# JacdacPinHeaders_45.net
KiCad netlist of a schematic drawn in Altium Designer
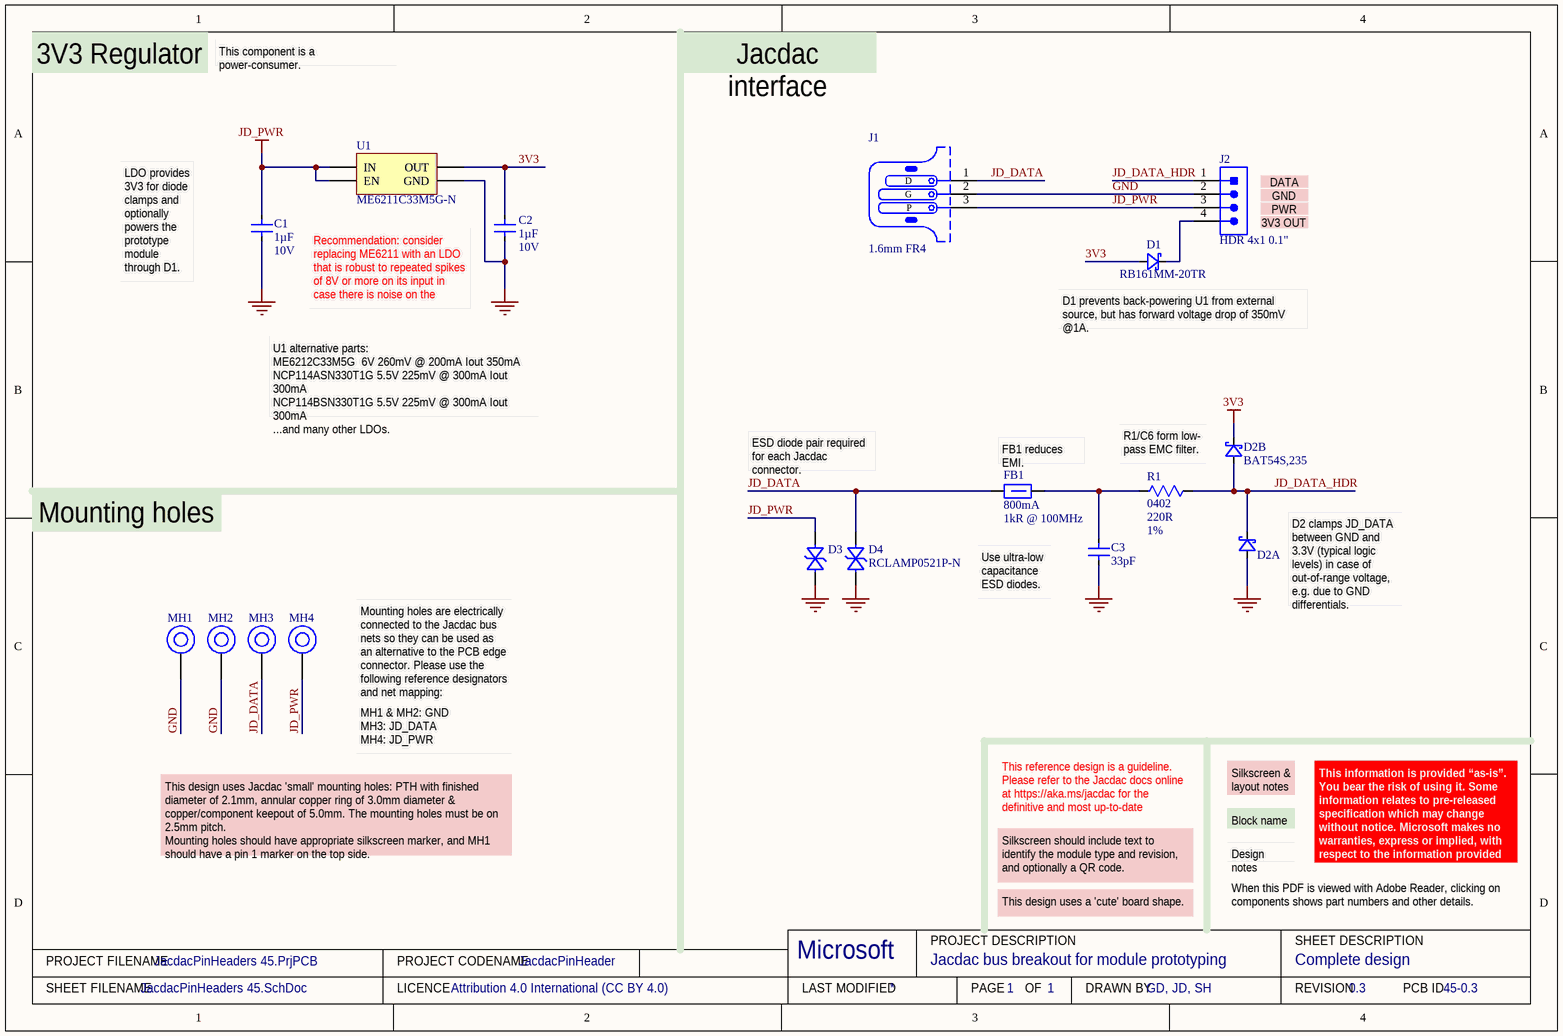
[diagram p0: JacdacPinHeaders 45.SchDoc]

(export (version "E")
  (design (tool "Eeschema 10.0.6"))
  (components
    (comp (ref "C1")
      (value "CL05A105KP5NNNC")
      (footprint "C0402_0.55MM - without outline")
      (description "CAP CER 1UF 10V X5R 0402")
      (fields
        (field (name "MANUFACTURER") "Samsung")
        (field (name "TOLERANCE") "10%")
        (field (name "CAPACITANCE") "1µF")
        (field (name "VOLTAGE RATING") "10V")
        (field (name "CREATED") "DG")
        (field (name "CHECKED") "?")
      )
      (libsource (lib "Samsung") (part "CL05A105KP5NNNC"))
    )
    (comp (ref "C2")
      (value "CL05A105KP5NNNC")
      (footprint "C0402_0.55MM - without outline")
      (description "CAP CER 1UF 10V X5R 0402")
      (fields
        (field (name "MANUFACTURER") "Samsung")
        (field (name "TOLERANCE") "10%")
        (field (name "CAPACITANCE") "1µF")
        (field (name "VOLTAGE RATING") "10V")
        (field (name "CREATED") "DG")
        (field (name "CHECKED") "?")
      )
      (libsource (lib "Samsung") (part "CL05A105KP5NNNC"))
    )
    (comp (ref "C3")
      (value "CL05C330JB51PNC")
      (footprint "C0402_0.55MM - without outline")
      (description "CAP CER 33PF 50V NP0 0402")
      (fields
        (field (name "MANUFACTURER") "Samsung")
        (field (name "TOLERANCE") "5%")
        (field (name "CAPACITANCE") "33pF")
        (field (name "CHECKED") "?")
        (field (name "CREATED") "DG")
      )
      (libsource (lib "Samsung") (part "CL05C330JB51PNC"))
    )
    (comp (ref "D1")
      (value "RB161MM-20TR")
      (footprint "SOD-123F")
      (description "ROHM - RB161MM-20TR - Schottky-Gleichrichterdiode, 20 V, 1 A, Einfach, SOD-123FL, 2 Pin(s), 350 mV")
      (fields (field (name "MANUFACTURER") "Rohm") (field (name "MANUFACTURER PART NUMBER") "RB161MM-20TR"))
      (libsource (lib "Rohm") (part "RB161MM-20TR"))
    )
    (comp (ref "D2")
      (value "BAT54S")
      (footprint "NXP-BAT54S-TO-236AB - without outline")
      (description "DIODE ARRAY SCHOTTKY 30V SOT23")
      (fields (field (name "MANUFACTURER") "Nexperia") (field (name "MANUFACTURER PART NUMBER") "BAT54S,235"))
      (libsource (lib "NXP") (part "BAT54S"))
    )
    (comp (ref "D3")
      (value "RCLAMP0521P-N")
      (footprint "TVS 0402 - L")
      (description "Bidirectional 5V (Max) 6V 16V 3.5A (8/20us) 0402 TVS RoHS")
      (fields
        (field (name "MANUFACTURER") "Born Semiconductor")
        (field (name "CREATED BY") "D Gakure")
        (field (name "CHECKED BY") "?")
      )
      (libsource (lib "BornSemiconductor") (part "RCLAMP0521P-N"))
    )
    (comp (ref "D4")
      (value "RCLAMP0521P-N")
      (footprint "TVS 0402 - L")
      (description "Bidirectional 5V (Max) 6V 16V 3.5A (8/20us) 0402 TVS RoHS")
      (fields
        (field (name "MANUFACTURER") "Born Semiconductor")
        (field (name "MANUFACTURER PART NUMBER") "RCLAMP0521P-N")
        (field (name "CREATED BY") "D Gakure")
        (field (name "CHECKED BY") "?")
      )
      (libsource (lib "BornSemiconductor") (part "RCLAMP0521P-N"))
    )
    (comp (ref "FB1")
      (value "TDK MPZ1608S102ATA00")
      (footprint "TDK MPZ1608 0.8mm - without outline")
      (description "0603 1k@100MHz 0.8A chip")
      (fields
        (field (name "TOLERANCE") "25%")
        (field (name "MANUFACTURER") "TDK")
        (field (name "CURRENT RATING") "800mA")
        (field (name "IMPEDANCE") "1kR @ 100MHz")
      )
      (libsource (lib "TDK") (part "TDK MPZ1608S102ATA00"))
    )
    (comp (ref "J1")
      (value "3 pin JACDAC edge connector")
      (footprint "JACDAC_EDGE_CONNECTOR_NO_TRACES")
      (description "3 pin Jacdac edge connector 1.27mm pitch")
      (fields
        (field (name "MANUFACTURER PART NUMBER") "JACDAC_EDGE_CONNECTOR")
        (field (name "PCB TYPE") "1.6mm FR4")
        (field (name "CHECKED BY") "?")
        (field (name "CREATED BY") "D. Gakure")
      )
      (libsource (lib "generic-con") (part "Jacdac edge connector"))
    )
    (comp (ref "J2")
      (value "HDR 4x1 0.1\"")
      (footprint "Generic 1x4 2.54mm header")
      (description "2.54mm, 4x1 way, vertical, square pin, gold plate")
      (fields
        (field (name "MANUFACTURER") "Multicomp")
        (field (name "MANUFACTURER PART NUMBER") "2211S-04G")
        (field (name "CREATED BY") "HUGHWI")
      )
      (libsource (lib "generic-con") (part "Header Multicomp 2211S-04G-whitesch"))
    )
    (comp (ref "MH1")
      (value "MH_5.0MMK_3.0MMC_2.1MMD_PTH")
      (footprint "MH_5.0MMK_3.0MMC_2.1MMD_PTH:MH_5.0MMK_3.0MMC_2.1MMD_PTH")
      (description "Mounting Hole 5.0mm keepout, 3.0mm annualar ring and 2.1mm Drill PTH")
      (libsource (lib "generic") (part "MH_5.0MMK_3.0MMC_2.1MMD_PTH"))
    )
    (comp (ref "MH2")
      (value "MH_5.0MMK_3.0MMC_2.1MMD_PTH")
      (footprint "MH_5.0MMK_3.0MMC_2.1MMD_PTH:MH_5.0MMK_3.0MMC_2.1MMD_PTH")
      (description "Mounting Hole 5.0mm keepout, 3.0mm annualar ring and 2.1mm Drill PTH")
      (libsource (lib "generic") (part "MH_5.0MMK_3.0MMC_2.1MMD_PTH"))
    )
    (comp (ref "MH3")
      (value "MH_5.0MMK_3.0MMC_2.1MMD_PTH")
      (footprint "MH_5.0MMK_3.0MMC_2.1MMD_PTH:MH_5.0MMK_3.0MMC_2.1MMD_PTH")
      (description "Mounting Hole 5.0mm keepout, 3.0mm annualar ring and 2.1mm Drill PTH")
      (libsource (lib "generic") (part "MH_5.0MMK_3.0MMC_2.1MMD_PTH"))
    )
    (comp (ref "MH4")
      (value "MH_5.0MMK_3.0MMC_2.1MMD_PTH")
      (footprint "MH_5.0MMK_3.0MMC_2.1MMD_PTH:MH_5.0MMK_3.0MMC_2.1MMD_PTH")
      (description "Mounting Hole 5.0mm keepout, 3.0mm annualar ring and 2.1mm Drill PTH")
      (libsource (lib "generic") (part "MH_5.0MMK_3.0MMC_2.1MMD_PTH"))
    )
    (comp (ref "R1")
      (value "RC0402FR-07220RL")
      (footprint "R0402 - Without outline")
      (description "RES SMD 220 OHM 1% 1/16W 0402")
      (fields
        (field (name "MANUFACTURER") "Yageo")
        (field (name "CASE CODE (IMPERIAL)") "0402")
        (field (name "RESISTANCE") "220R")
        (field (name "TOLERANCE") "1%")
        (field (name "CREATED") "D.G")
        (field (name "CHECKED") "?")
      )
      (libsource (lib "Yageo") (part "RC0402FR-07220RL"))
    )
    (comp (ref "U1")
      (value "ME6211C33M5G-N")
      (footprint "MICRONE-SOT23-5")
      (description "6V 260mV @ 200mA(typ) - - Fixed 3.3V SOT-23-5 Linear Voltage Regulators (LDO) ROHS")
      (fields
        (field (name "MANUFACTURER") "MICRONE(Nanjing Micro One Elec)")
        (field (name "MANUFACTURER PART NUMBER") "ME6211C33M5G-N")
        (field (name "CREATED") "DG")
        (field (name "CHECKED") "?")
      )
      (libsource (lib "MICRONE(NanjingMicroOneElec)") (part "ME6211C33M5G-N"))
    )
  )
  (nets
    (net (code "1") (name "/JD_DATA") (class "Default")
      (node (ref "D4") (pin "1") (pinfunction "K_1") (pintype "passive"))
      (node (ref "FB1") (pin "1") (pinfunction "1_1") (pintype "passive"))
      (node (ref "J1") (pin "1") (pinfunction "D_1") (pintype "passive"))
      (node (ref "MH3") (pin "1") (pinfunction "1_1") (pintype "passive"))
    )
    (net (code "2") (name "/JD_DATA_HDR") (class "Default")
      (node (ref "D2") (pin "3") (pinfunction "K_3") (pintype "passive"))
      (node (ref "J2") (pin "1") (pinfunction "1_1") (pintype "passive"))
      (node (ref "R1") (pin "1") (pinfunction "1_1") (pintype "passive"))
    )
    (net (code "3") (name "3V3") (class "Default")
      (node (ref "C2") (pin "2") (pinfunction "2_2") (pintype "passive"))
      (node (ref "D1") (pin "2") (pinfunction "A_2") (pintype "passive"))
      (node (ref "D2") (pin "2") (pinfunction "K_2") (pintype "passive"))
      (node (ref "U1") (pin "5") (pinfunction "OUT_5") (pintype "passive"))
    )
    (net (code "4") (name "GND") (class "Default")
      (node (ref "C1") (pin "1") (pinfunction "1_1") (pintype "passive"))
      (node (ref "C2") (pin "1") (pinfunction "1_1") (pintype "passive"))
      (node (ref "C3") (pin "1") (pinfunction "1_1") (pintype "passive"))
      (node (ref "D2") (pin "1") (pinfunction "A_1") (pintype "passive"))
      (node (ref "D3") (pin "2") (pinfunction "A_2") (pintype "passive"))
      (node (ref "D4") (pin "2") (pinfunction "A_2") (pintype "passive"))
      (node (ref "J1") (pin "2") (pinfunction "G_2") (pintype "passive"))
      (node (ref "J2") (pin "2") (pinfunction "2_2") (pintype "passive"))
      (node (ref "MH1") (pin "1") (pinfunction "1_1") (pintype "passive"))
      (node (ref "MH2") (pin "1") (pinfunction "1_1") (pintype "passive"))
      (node (ref "U1") (pin "2") (pinfunction "GND_2") (pintype "passive"))
    )
    (net (code "5") (name "JD_PWR") (class "Default")
      (node (ref "C1") (pin "2") (pinfunction "2_2") (pintype "passive"))
      (node (ref "D3") (pin "1") (pinfunction "K_1") (pintype "passive"))
      (node (ref "J1") (pin "3") (pinfunction "P_3") (pintype "passive"))
      (node (ref "J2") (pin "3") (pinfunction "3_3") (pintype "passive"))
      (node (ref "MH4") (pin "1") (pinfunction "1_1") (pintype "passive"))
      (node (ref "U1") (pin "1") (pinfunction "IN_1") (pintype "passive"))
      (node (ref "U1") (pin "3") (pinfunction "EN_3") (pintype "passive"))
    )
    (net (code "6") (name "Net-(C3-Pad2)") (class "Default")
      (node (ref "C3") (pin "2") (pinfunction "2_2") (pintype "passive"))
      (node (ref "FB1") (pin "2") (pinfunction "2_2") (pintype "passive"))
      (node (ref "R1") (pin "2") (pinfunction "2_2") (pintype "passive"))
    )
    (net (code "7") (name "Net-(D1-K)") (class "Default")
      (node (ref "D1") (pin "1") (pinfunction "K_1") (pintype "passive"))
      (node (ref "J2") (pin "4") (pinfunction "4_4") (pintype "passive"))
    )
  )
)
